# driver.net
KiCad netlist of a schematic drawn in EAGLE
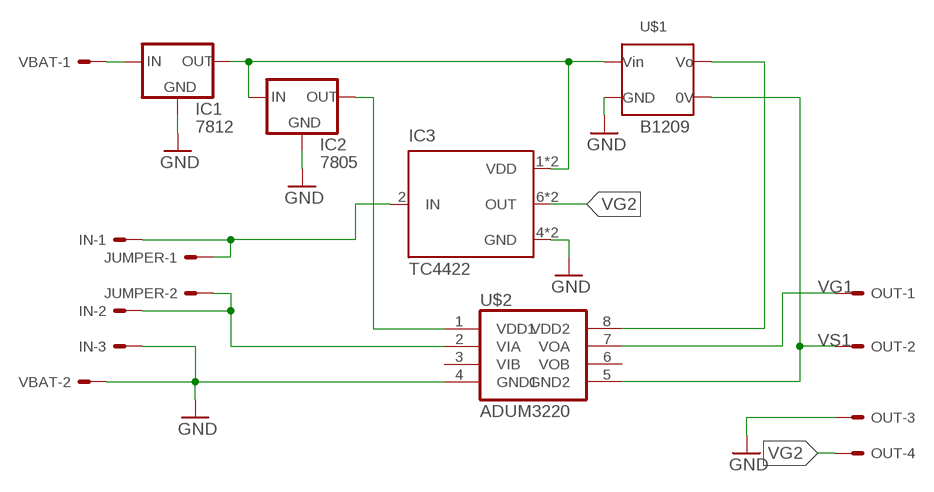
[diagram p0: schematic, sheet 1]

(export (version "E")
  (design (tool "Eeschema 10.0.6"))
  (components
    (comp (ref "IC1")
      (value "7812")
      (footprint "eagle-import:78XXS")
      (libsource (lib "eagle-import") (part "78XXS"))
    )
    (comp (ref "IC2")
      (value "7805")
      (footprint "eagle-import:78XXS")
      (libsource (lib "eagle-import") (part "78XXS"))
    )
    (comp (ref "IC3")
      (value "TC4422")
      (footprint "eagle-import:DIL08")
      (fields (field (name "MF") "INTERNATIONAL RECTIFIER(IR)") (field (name "MPN") "IR4426PBF"))
      (libsource (lib "eagle-import") (part "TC4422"))
    )
    (comp (ref "IN")
      (value "22-23-2031")
      (footprint "eagle-import:22-23-2031")
      (fields (field (name "MF") "MOLEX"))
      (libsource (lib "eagle-import") (part "22-23-2031"))
    )
    (comp (ref "JUMPER")
      (value "22-23-2021")
      (footprint "eagle-import:22-23-2021")
      (fields (field (name "MF") "MOLEX"))
      (libsource (lib "eagle-import") (part "22-23-2021"))
    )
    (comp (ref "OUT")
      (value "22-23-2041")
      (footprint "eagle-import:22-23-2041")
      (fields (field (name "MF") "MOLEX"))
      (libsource (lib "eagle-import") (part "22-23-2041"))
    )
    (comp (ref "U$1")
      (value "B1209")
      (footprint "eagle-import:22-23-2041")
      (libsource (lib "eagle-import") (part "B1209"))
    )
    (comp (ref "U$2")
      (value "ADUM3220")
      (footprint "eagle-import:SO8")
      (libsource (lib "eagle-import") (part "ADUM3220"))
    )
    (comp (ref "VBAT")
      (value "22-23-2021")
      (footprint "eagle-import:22-23-2021")
      (fields (field (name "MF") "MOLEX"))
      (libsource (lib "eagle-import") (part "22-23-2021"))
    )
  )
  (nets
    (net (code "1") (name "/VG1") (class "Default")
      (node (ref "OUT") (pin "1") (pinfunction "S_1") (pintype "passive"))
      (node (ref "U$2") (pin "7") (pinfunction "VOA_7") (pintype "output"))
    )
    (net (code "2") (name "/VS1") (class "Default")
      (node (ref "OUT") (pin "2") (pinfunction "S_2") (pintype "passive"))
      (node (ref "U$1") (pin "3") (pinfunction "0V_3") (pintype "passive"))
      (node (ref "U$2") (pin "5") (pinfunction "GND2_5") (pintype "output"))
    )
    (net (code "3") (name "GND") (class "Default")
      (node (ref "IC1") (pin "GND") (pinfunction "GND_GND") (pintype "input"))
      (node (ref "IC2") (pin "GND") (pinfunction "GND_GND") (pintype "input"))
      (node (ref "IC3") (pin "4") (pinfunction "GND_4") (pintype "power_in"))
      (node (ref "IC3") (pin "5") (pinfunction "GND_5") (pintype "power_in"))
      (node (ref "IN") (pin "3") (pinfunction "S_3") (pintype "passive"))
      (node (ref "OUT") (pin "3") (pinfunction "S_3") (pintype "passive"))
      (node (ref "U$1") (pin "1") (pinfunction "GND_1") (pintype "passive"))
      (node (ref "U$2") (pin "4") (pinfunction "GND1_4") (pintype "input"))
      (node (ref "VBAT") (pin "2") (pinfunction "S_2") (pintype "passive"))
    )
    (net (code "4") (name "Net-(IC3-IN)") (class "Default")
      (node (ref "IC3") (pin "2") (pinfunction "IN_2") (pintype "input"))
      (node (ref "IN") (pin "1") (pinfunction "S_1") (pintype "passive"))
      (node (ref "JUMPER") (pin "1") (pinfunction "S_1") (pintype "passive"))
    )
    (net (code "5") (name "Net-(INB-S)") (class "Default")
      (node (ref "IN") (pin "2") (pinfunction "S_2") (pintype "passive"))
      (node (ref "JUMPER") (pin "2") (pinfunction "S_2") (pintype "passive"))
      (node (ref "U$2") (pin "2") (pinfunction "VIA_2") (pintype "input"))
    )
    (net (code "6") (name "Net-(U$1-VIN)") (class "Default")
      (node (ref "IC1") (pin "OUT") (pinfunction "OUT_OUT") (pintype "passive"))
      (node (ref "IC2") (pin "IN") (pinfunction "IN_IN") (pintype "input"))
      (node (ref "IC3") (pin "1") (pinfunction "VDD_1") (pintype "power_in"))
      (node (ref "IC3") (pin "8") (pinfunction "VDD_8") (pintype "power_in"))
      (node (ref "U$1") (pin "2") (pinfunction "VIN_2") (pintype "passive"))
    )
    (net (code "7") (name "Net-(U$1-VO)") (class "Default")
      (node (ref "U$1") (pin "4") (pinfunction "VO_4") (pintype "passive"))
      (node (ref "U$2") (pin "8") (pinfunction "VDD2_8") (pintype "output"))
    )
    (net (code "8") (name "Net-(U$2-VDD1)") (class "Default")
      (node (ref "IC2") (pin "OUT") (pinfunction "OUT_OUT") (pintype "passive"))
      (node (ref "U$2") (pin "1") (pinfunction "VDD1_1") (pintype "input"))
    )
    (net (code "9") (name "Net-(VBATA-S)") (class "Default")
      (node (ref "IC1") (pin "IN") (pinfunction "IN_IN") (pintype "input"))
      (node (ref "VBAT") (pin "1") (pinfunction "S_1") (pintype "passive"))
    )
    (net (code "10") (name "VG2") (class "Default")
      (node (ref "IC3") (pin "6") (pinfunction "OUT_6") (pintype "output"))
      (node (ref "IC3") (pin "7") (pinfunction "OUT_7") (pintype "output"))
      (node (ref "OUT") (pin "4") (pinfunction "S_4") (pintype "passive"))
    )
    (net (code "11") (name "unconnected-(U$2-VIB-Pad3)") (class "Default")
      (node (ref "U$2") (pin "3") (pinfunction "VIB_3") (pintype "input"))
    )
    (net (code "12") (name "unconnected-(U$2-VOB-Pad6)") (class "Default")
      (node (ref "U$2") (pin "6") (pinfunction "VOB_6") (pintype "output"))
    )
  )
)
